# RS232_Loopback.net
KiCad netlist of a schematic drawn in EAGLE
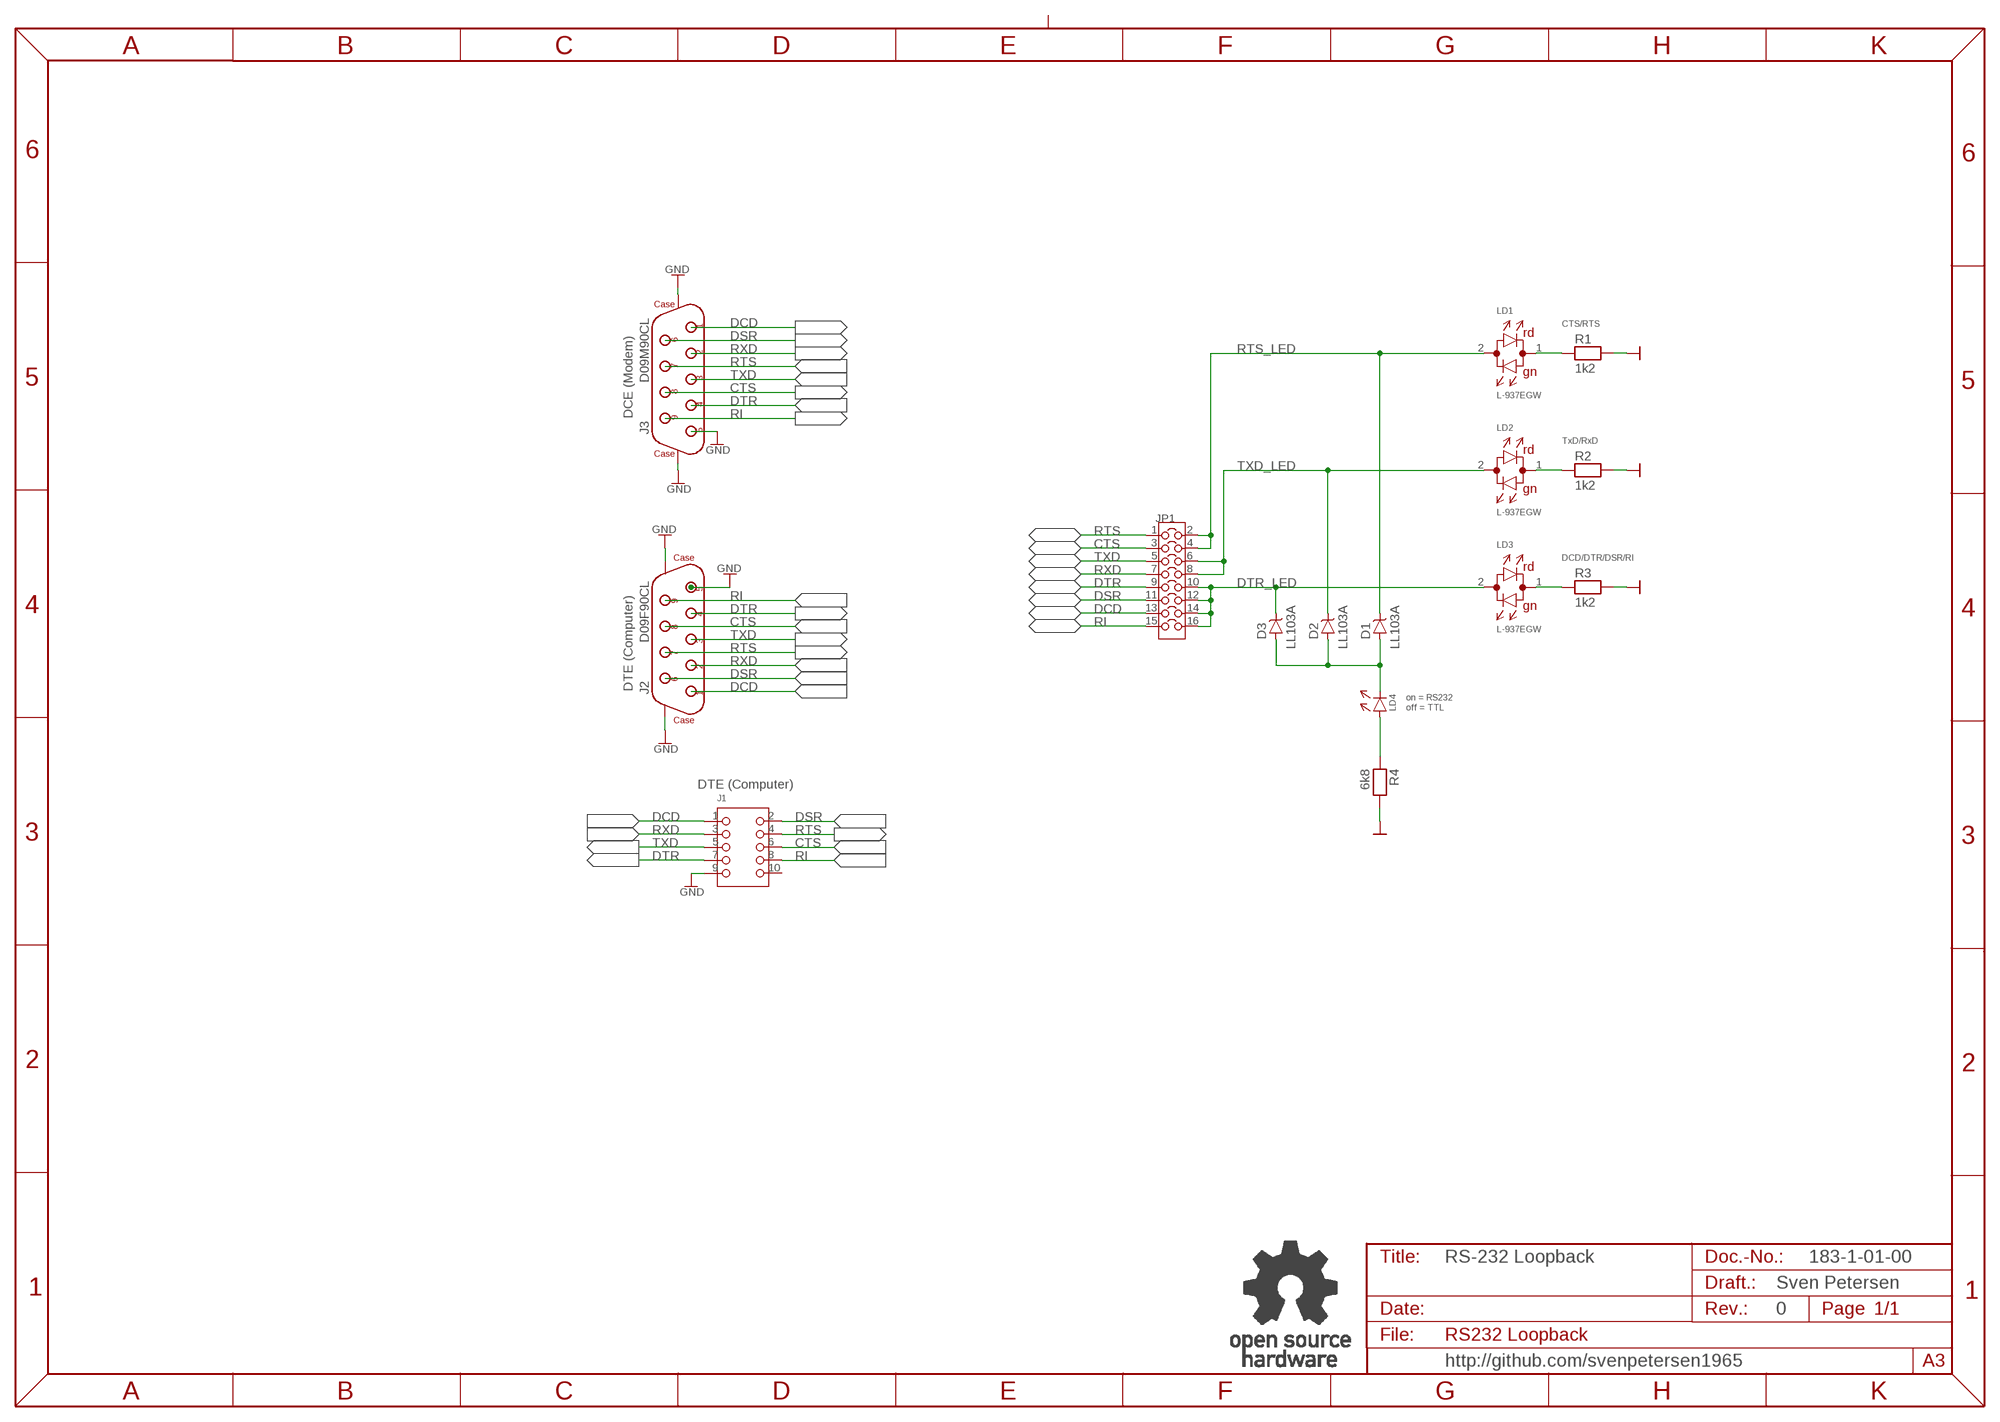
[diagram p0: schematic, sheet 1]

(export (version "E")
  (design (tool "Eeschema 10.0.6"))
  (components
    (comp (ref "D1")
      (value "LL103A")
      (footprint "eagle-import:SOD80C")
      (libsource (lib "eagle-import") (part "LL103A"))
    )
    (comp (ref "D2")
      (value "LL103A")
      (footprint "eagle-import:SOD80C")
      (libsource (lib "eagle-import") (part "LL103A"))
    )
    (comp (ref "D3")
      (value "LL103A")
      (footprint "eagle-import:SOD80C")
      (libsource (lib "eagle-import") (part "LL103A"))
    )
    (comp (ref "J1")
      (value "2X05WV")
      (footprint "eagle-import:2X05WV")
      (libsource (lib "eagle-import") (part "2X05WV"))
    )
    (comp (ref "J2")
      (value "D09F90CL")
      (footprint "eagle-import:D09F90CL")
      (libsource (lib "eagle-import") (part "D09F90CL"))
    )
    (comp (ref "J3")
      (value "D09M90CL")
      (footprint "eagle-import:D09M90CL")
      (libsource (lib "eagle-import") (part "D09M90CL"))
    )
    (comp (ref "JP1")
      (value "COMBI-8X2P")
      (footprint "eagle-import:COMBI-8X2")
      (libsource (lib "eagle-import") (part "COMBI-8X2P"))
    )
    (comp (ref "LD1")
      (value "L-937EGW")
      (footprint "eagle-import:LED_3MM_BICOLOR")
      (libsource (lib "eagle-import") (part "L-937EGW"))
    )
    (comp (ref "LD2")
      (value "L-937EGW")
      (footprint "eagle-import:LED_3MM_BICOLOR")
      (libsource (lib "eagle-import") (part "L-937EGW"))
    )
    (comp (ref "LD3")
      (value "L-937EGW")
      (footprint "eagle-import:LED_3MM_BICOLOR")
      (libsource (lib "eagle-import") (part "L-937EGW"))
    )
    (comp (ref "LD4")
      (value "3MM")
      (footprint "eagle-import:3MM")
      (libsource (lib "eagle-import") (part "3MM"))
    )
    (comp (ref "R1")
      (value "1k2")
      (footprint "eagle-import:0805")
      (libsource (lib "eagle-import") (part "R-0805"))
    )
    (comp (ref "R2")
      (value "1k2")
      (footprint "eagle-import:0805")
      (libsource (lib "eagle-import") (part "R-0805"))
    )
    (comp (ref "R3")
      (value "1k2")
      (footprint "eagle-import:0805")
      (libsource (lib "eagle-import") (part "R-0805"))
    )
    (comp (ref "R4")
      (value "6k8")
      (footprint "eagle-import:0805")
      (libsource (lib "eagle-import") (part "R-0805"))
    )
    (comp (ref "U$44")
      (value "OPEN_SOURCE_HW")
      (footprint "eagle-import:OPENHW")
      (libsource (lib "eagle-import") (part "OPEN_SOURCE_HW"))
    )
  )
  (nets
    (net (code "1") (name "/CTS") (class "Default")
      (node (ref "J1") (pin "6") (pinfunction "6_6") (pintype "passive"))
      (node (ref "J2") (pin "8") (pinfunction "8_8") (pintype "passive"))
      (node (ref "J3") (pin "8") (pinfunction "8_8") (pintype "passive"))
      (node (ref "JP1") (pin "3") (pinfunction "3_3") (pintype "bidirectional"))
    )
    (net (code "2") (name "/DCD") (class "Default")
      (node (ref "J1") (pin "1") (pinfunction "1_1") (pintype "passive"))
      (node (ref "J2") (pin "1") (pinfunction "1_1") (pintype "passive"))
      (node (ref "J3") (pin "1") (pinfunction "1_1") (pintype "passive"))
      (node (ref "JP1") (pin "13") (pinfunction "13_13") (pintype "bidirectional"))
    )
    (net (code "3") (name "/DSR") (class "Default")
      (node (ref "J1") (pin "2") (pinfunction "2_2") (pintype "passive"))
      (node (ref "J2") (pin "6") (pinfunction "6_6") (pintype "passive"))
      (node (ref "J3") (pin "6") (pinfunction "6_6") (pintype "passive"))
      (node (ref "JP1") (pin "11") (pinfunction "11_11") (pintype "bidirectional"))
    )
    (net (code "4") (name "/DTR") (class "Default")
      (node (ref "J1") (pin "7") (pinfunction "7_7") (pintype "passive"))
      (node (ref "J2") (pin "4") (pinfunction "4_4") (pintype "passive"))
      (node (ref "J3") (pin "4") (pinfunction "4_4") (pintype "passive"))
      (node (ref "JP1") (pin "9") (pinfunction "9_9") (pintype "bidirectional"))
    )
    (net (code "5") (name "/DTR_LED") (class "Default")
      (node (ref "D3") (pin "K") (pinfunction "K_K") (pintype "passive"))
      (node (ref "JP1") (pin "10") (pinfunction "10_10") (pintype "bidirectional"))
      (node (ref "JP1") (pin "12") (pinfunction "12_12") (pintype "bidirectional"))
      (node (ref "JP1") (pin "14") (pinfunction "14_14") (pintype "bidirectional"))
      (node (ref "JP1") (pin "16") (pinfunction "16_16") (pintype "bidirectional"))
      (node (ref "LD3") (pin "2") (pinfunction "2_2") (pintype "bidirectional"))
    )
    (net (code "6") (name "/RI") (class "Default")
      (node (ref "J1") (pin "8") (pinfunction "8_8") (pintype "passive"))
      (node (ref "J2") (pin "9") (pinfunction "9_9") (pintype "passive"))
      (node (ref "J3") (pin "9") (pinfunction "9_9") (pintype "passive"))
      (node (ref "JP1") (pin "15") (pinfunction "15_15") (pintype "bidirectional"))
    )
    (net (code "7") (name "/RTS") (class "Default")
      (node (ref "J1") (pin "4") (pinfunction "4_4") (pintype "passive"))
      (node (ref "J2") (pin "7") (pinfunction "7_7") (pintype "passive"))
      (node (ref "J3") (pin "7") (pinfunction "7_7") (pintype "passive"))
      (node (ref "JP1") (pin "1") (pinfunction "1_1") (pintype "bidirectional"))
    )
    (net (code "8") (name "/RTS_LED") (class "Default")
      (node (ref "D1") (pin "K") (pinfunction "K_K") (pintype "passive"))
      (node (ref "JP1") (pin "2") (pinfunction "2_2") (pintype "bidirectional"))
      (node (ref "JP1") (pin "4") (pinfunction "4_4") (pintype "bidirectional"))
      (node (ref "LD1") (pin "2") (pinfunction "2_2") (pintype "bidirectional"))
    )
    (net (code "9") (name "/RXD") (class "Default")
      (node (ref "J1") (pin "3") (pinfunction "3_3") (pintype "passive"))
      (node (ref "J2") (pin "2") (pinfunction "2_2") (pintype "passive"))
      (node (ref "J3") (pin "2") (pinfunction "2_2") (pintype "passive"))
      (node (ref "JP1") (pin "7") (pinfunction "7_7") (pintype "bidirectional"))
    )
    (net (code "10") (name "/TXD") (class "Default")
      (node (ref "J1") (pin "5") (pinfunction "5_5") (pintype "passive"))
      (node (ref "J2") (pin "3") (pinfunction "3_3") (pintype "passive"))
      (node (ref "J3") (pin "3") (pinfunction "3_3") (pintype "passive"))
      (node (ref "JP1") (pin "5") (pinfunction "5_5") (pintype "bidirectional"))
    )
    (net (code "11") (name "/TXD_LED") (class "Default")
      (node (ref "D2") (pin "K") (pinfunction "K_K") (pintype "passive"))
      (node (ref "JP1") (pin "6") (pinfunction "6_6") (pintype "bidirectional"))
      (node (ref "JP1") (pin "8") (pinfunction "8_8") (pintype "bidirectional"))
      (node (ref "LD2") (pin "2") (pinfunction "2_2") (pintype "bidirectional"))
    )
    (net (code "12") (name "GND") (class "Default")
      (node (ref "J1") (pin "9") (pinfunction "9_9") (pintype "passive"))
      (node (ref "J2") (pin "5") (pinfunction "5_5") (pintype "passive"))
      (node (ref "J2") (pin "CL1") (pinfunction "CASE1_CL1") (pintype "bidirectional"))
      (node (ref "J2") (pin "CL2") (pinfunction "CASE2_CL2") (pintype "bidirectional"))
      (node (ref "J3") (pin "5") (pinfunction "5_5") (pintype "passive"))
      (node (ref "J3") (pin "CL1") (pinfunction "CASE1_CL1") (pintype "bidirectional"))
      (node (ref "J3") (pin "CL2") (pinfunction "CASE2_CL2") (pintype "bidirectional"))
      (node (ref "R1") (pin "2") (pinfunction "2_2") (pintype "passive"))
      (node (ref "R2") (pin "2") (pinfunction "2_2") (pintype "passive"))
      (node (ref "R3") (pin "2") (pinfunction "2_2") (pintype "passive"))
      (node (ref "R4") (pin "2") (pinfunction "2_2") (pintype "passive"))
    )
    (net (code "13") (name "Net-(LD1-Pad1)") (class "Default")
      (node (ref "LD1") (pin "1") (pinfunction "1_1") (pintype "bidirectional"))
      (node (ref "R1") (pin "1") (pinfunction "1_1") (pintype "passive"))
    )
    (net (code "14") (name "Net-(LD2-Pad1)") (class "Default")
      (node (ref "LD2") (pin "1") (pinfunction "1_1") (pintype "bidirectional"))
      (node (ref "R2") (pin "1") (pinfunction "1_1") (pintype "passive"))
    )
    (net (code "15") (name "Net-(LD3-Pad1)") (class "Default")
      (node (ref "LD3") (pin "1") (pinfunction "1_1") (pintype "bidirectional"))
      (node (ref "R3") (pin "1") (pinfunction "1_1") (pintype "passive"))
    )
    (net (code "16") (name "Net-(LD4-K)") (class "Default")
      (node (ref "D1") (pin "A") (pinfunction "A_A") (pintype "passive"))
      (node (ref "D2") (pin "A") (pinfunction "A_A") (pintype "passive"))
      (node (ref "D3") (pin "A") (pinfunction "A_A") (pintype "passive"))
      (node (ref "LD4") (pin "C") (pinfunction "K_C") (pintype "bidirectional"))
    )
    (net (code "17") (name "Net-(LD4-PadA)") (class "Default")
      (node (ref "LD4") (pin "A") (pinfunction "A_A") (pintype "bidirectional"))
      (node (ref "R4") (pin "1") (pinfunction "1_1") (pintype "passive"))
    )
    (net (code "18") (name "unconnected-(J1-Pad10)") (class "Default")
      (node (ref "J1") (pin "10") (pinfunction "10_10") (pintype "passive"))
    )
  )
)
